# VIVA_PIC16_REV4-5.net
KiCad netlist of a schematic drawn in EAGLE
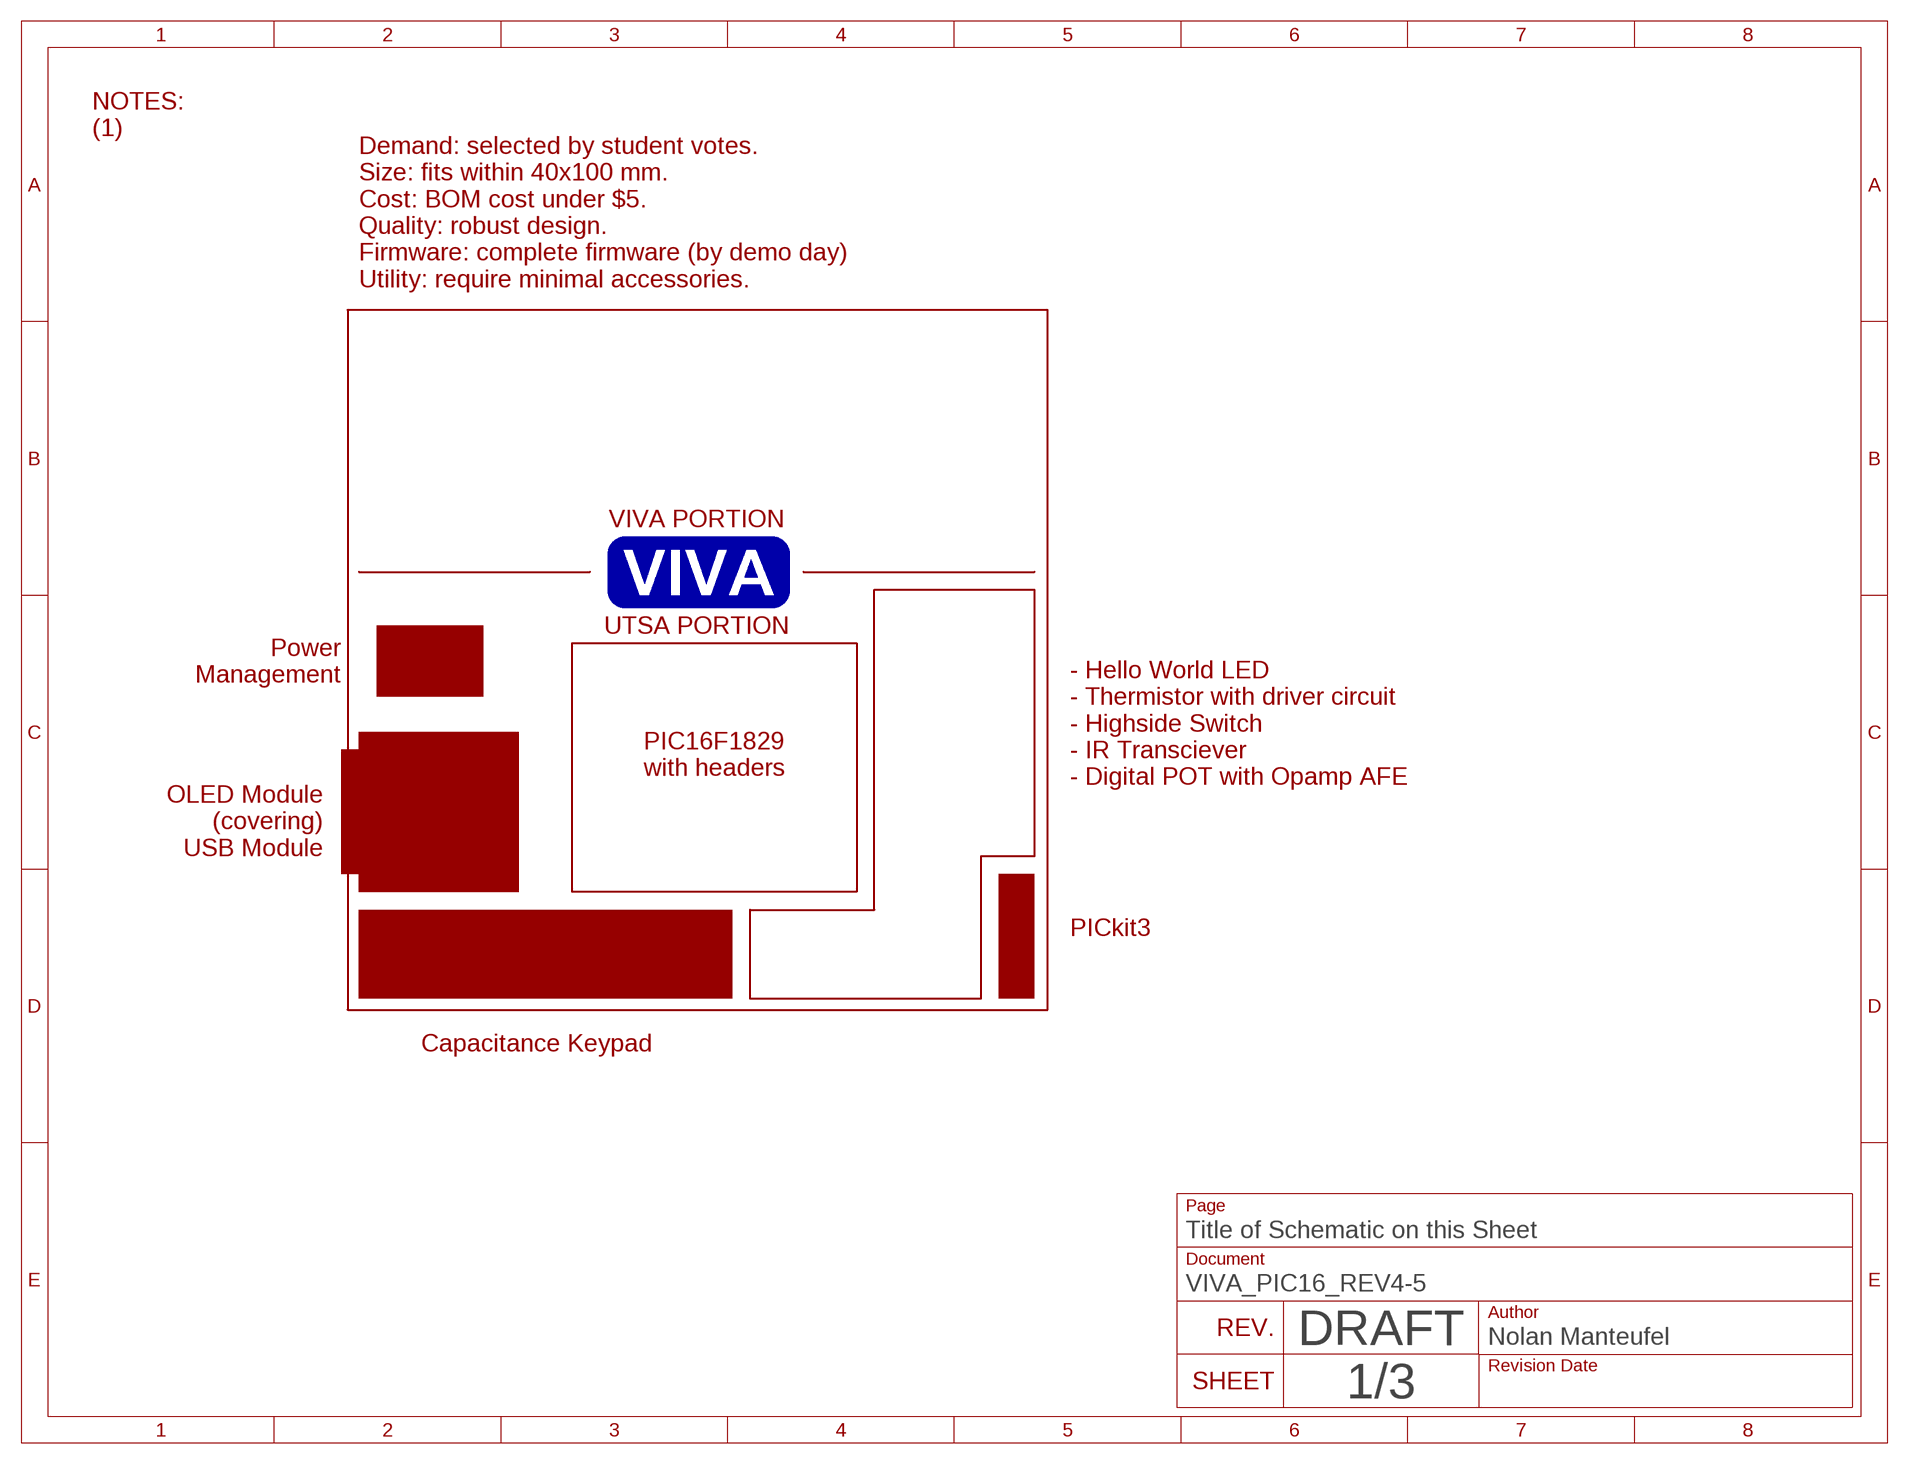
[diagram p0: schematic, sheet 1]
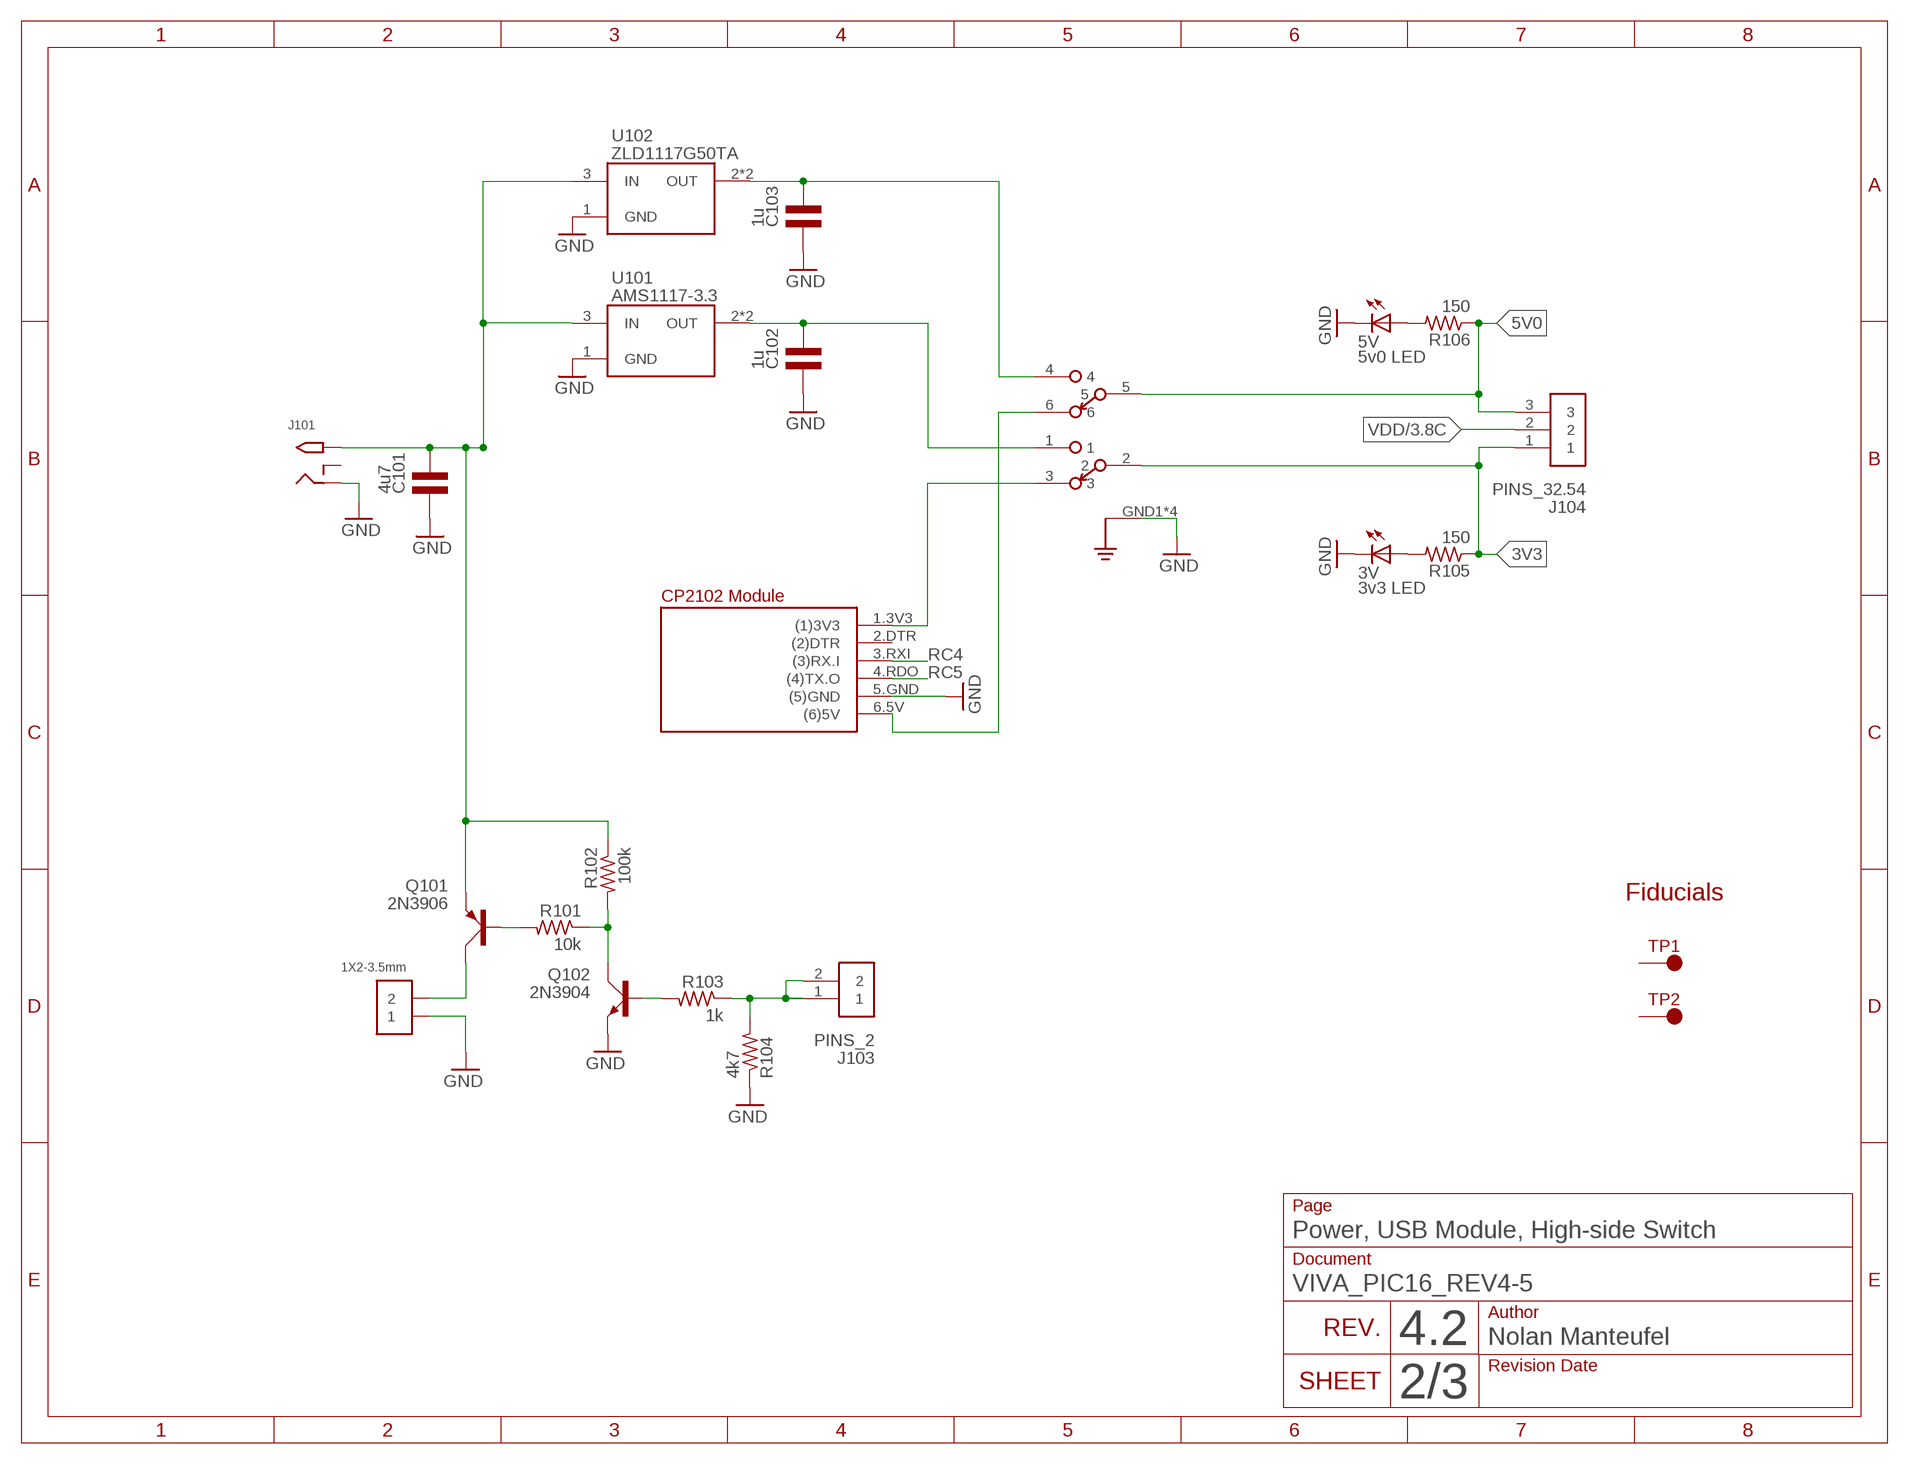
[diagram p1: schematic, sheet 2]
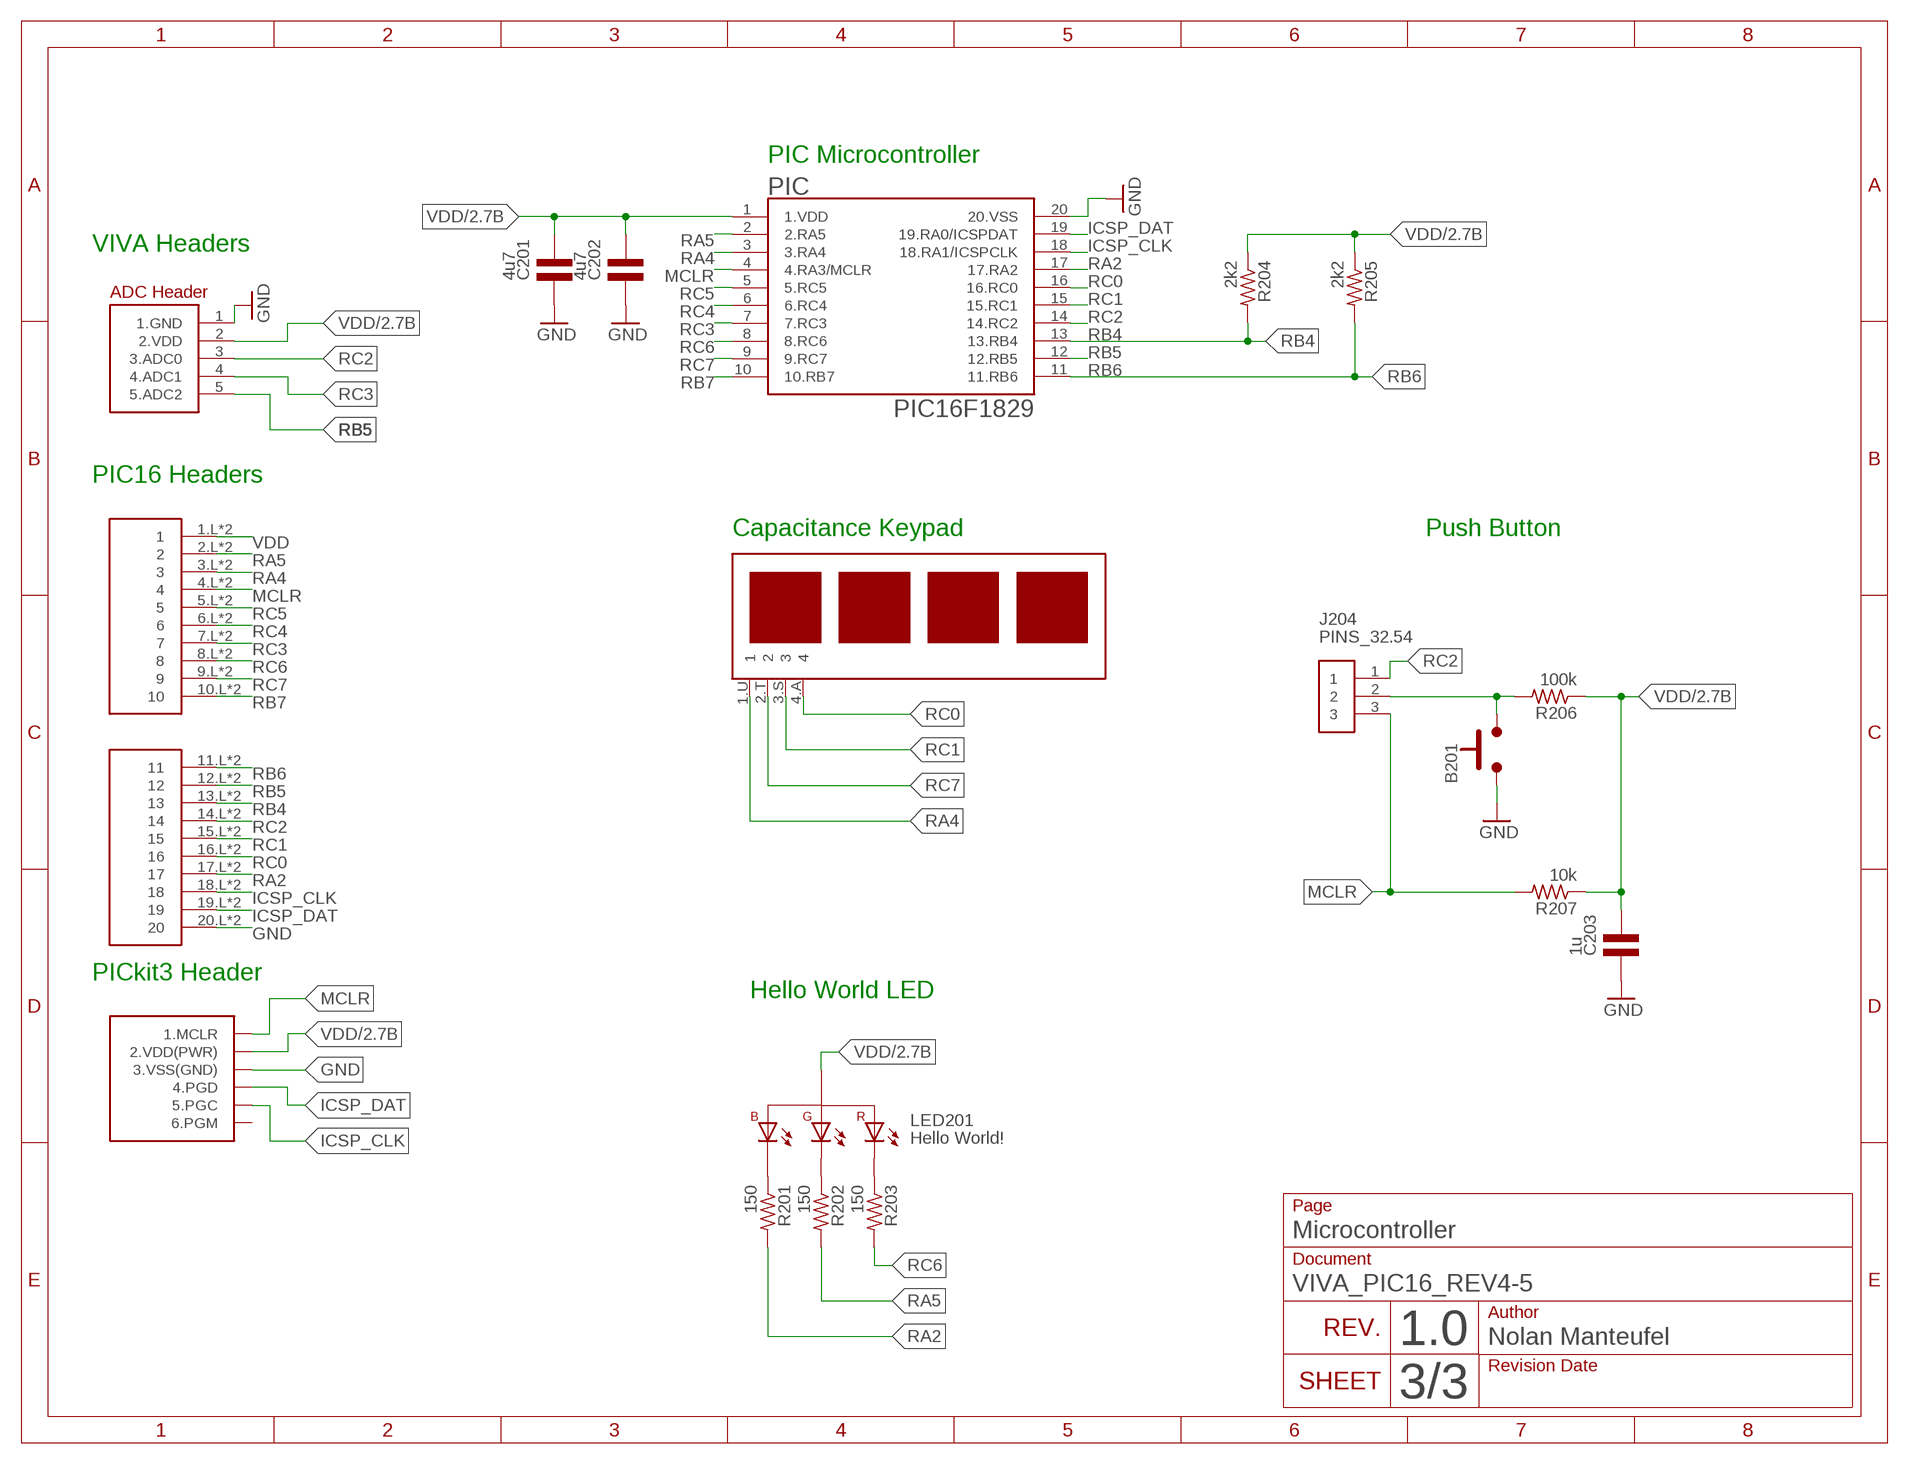
[diagram p2: schematic, sheet 3]

(export (version "E")
  (design (tool "Eeschema 10.0.6"))
  (components
    (comp (ref "3V")
      (value "3v3 LED")
      (footprint "eagle-import:CHIPLED_0805")
      (libsource (lib "eagle-import") (part "LEDCHIPLED_0805"))
    )
    (comp (ref "5V")
      (value "5v0 LED")
      (footprint "eagle-import:CHIPLED_0805")
      (libsource (lib "eagle-import") (part "LEDCHIPLED_0805"))
    )
    (comp (ref "C101")
      (value "4u7")
      (footprint "eagle-import:C0805")
      (libsource (lib "eagle-import") (part "C0805"))
    )
    (comp (ref "C102")
      (value "1u")
      (footprint "eagle-import:C0805")
      (libsource (lib "eagle-import") (part "C0805"))
    )
    (comp (ref "C103")
      (value "1u")
      (footprint "eagle-import:C0805")
      (libsource (lib "eagle-import") (part "C0805"))
    )
    (comp (ref "J101")
      (value "2.1MMJACKTHM")
      (footprint "eagle-import:PJ-102A")
      (libsource (lib "eagle-import") (part "2.1MMJACKTHM"))
    )
    (comp (ref "J102")
      (value "1X2-3.5MM-3.5MM")
      (footprint "eagle-import:1X2-3.5MM")
      (libsource (lib "eagle-import") (part "1X2-3.5MM-3.5MM"))
    )
    (comp (ref "J103")
      (value "PINS_2")
      (footprint "eagle-import:PINS_2")
      (libsource (lib "eagle-import") (part "PINS_2"))
    )
    (comp (ref "J104")
      (value "PINS_32.54")
      (footprint "eagle-import:PINS_3")
      (libsource (lib "eagle-import") (part "PINS_32.54"))
    )
    (comp (ref "M101")
      (value "VIVA_USB-TTL")
      (footprint "eagle-import:VIVA_USB_TTL_SUBTEXT")
      (libsource (lib "eagle-import") (part "VIVA_USB-TTL"))
    )
    (comp (ref "Q101")
      (value "2N3906")
      (footprint "eagle-import:SOT23")
      (libsource (lib "eagle-import") (part "2N3906SOT23"))
    )
    (comp (ref "Q102")
      (value "2N3904")
      (footprint "eagle-import:SOT23")
      (libsource (lib "eagle-import") (part "2N3904SOT23"))
    )
    (comp (ref "R101")
      (value "10k")
      (footprint "eagle-import:R0805")
      (libsource (lib "eagle-import") (part "R-US_R0805"))
    )
    (comp (ref "R102")
      (value "100k")
      (footprint "eagle-import:R0805")
      (libsource (lib "eagle-import") (part "R-US_R0805"))
    )
    (comp (ref "R103")
      (value "1k")
      (footprint "eagle-import:R0805")
      (libsource (lib "eagle-import") (part "R-US_R0805"))
    )
    (comp (ref "R104")
      (value "4k7")
      (footprint "eagle-import:R0805")
      (libsource (lib "eagle-import") (part "R-US_R0805"))
    )
    (comp (ref "R105")
      (value "150")
      (footprint "eagle-import:R0805")
      (libsource (lib "eagle-import") (part "R-US_R0805"))
    )
    (comp (ref "R106")
      (value "150")
      (footprint "eagle-import:R0805")
      (libsource (lib "eagle-import") (part "R-US_R0805"))
    )
    (comp (ref "S101")
      (value "SWITCH_OS202013")
      (footprint "eagle-import:OS202013MT5QN1")
      (libsource (lib "eagle-import") (part "SWITCH_OS202013"))
    )
    (comp (ref "TP1")
      (value "TESTPOINTFIDUCIAL")
      (footprint "eagle-import:FIDUCIAL")
      (libsource (lib "eagle-import") (part "TESTPOINTFIDUCIAL"))
    )
    (comp (ref "TP2")
      (value "TESTPOINTFIDUCIAL")
      (footprint "eagle-import:FIDUCIAL")
      (libsource (lib "eagle-import") (part "TESTPOINTFIDUCIAL"))
    )
    (comp (ref "U101")
      (value "AMS1117-3.3")
      (footprint "eagle-import:SOT223")
      (libsource (lib "eagle-import") (part "REGULATOR_SCHLM1117"))
    )
    (comp (ref "U102")
      (value "ZLD1117G50TA")
      (footprint "eagle-import:SOT223")
      (libsource (lib "eagle-import") (part "REGULATOR_SCHLM1117"))
    )
    (comp (ref "U$1")
      (value "VIVA_LOGO")
      (footprint "eagle-import:VIVA_LOGO")
      (libsource (lib "eagle-import") (part "VIVA_LOGO"))
    )
    (comp (ref "B201")
      (value "PUSHBUTTON6X6MM")
      (footprint "eagle-import:6X6MM")
      (libsource (lib "eagle-import") (part "PUSHBUTTON6X6MM"))
    )
    (comp (ref "C201")
      (value "4u7")
      (footprint "eagle-import:C0805")
      (libsource (lib "eagle-import") (part "C0805"))
    )
    (comp (ref "C202")
      (value "4u7")
      (footprint "eagle-import:C0805")
      (libsource (lib "eagle-import") (part "C0805"))
    )
    (comp (ref "C203")
      (value "1u")
      (footprint "eagle-import:C0805")
      (libsource (lib "eagle-import") (part "C0805"))
    )
    (comp (ref "J201")
      (value "VIVA_PIC16")
      (footprint "eagle-import:VIVA_PIC16")
      (libsource (lib "eagle-import") (part "VIVA_PIC16"))
    )
    (comp (ref "J202")
      (value "VIVA-HEADER-ADCNONAME")
      (footprint "eagle-import:VIVA-HEADER-ADC-NONAME")
      (libsource (lib "eagle-import") (part "VIVA-HEADER-ADCNONAME"))
    )
    (comp (ref "J203")
      (value "PICKIT3")
      (footprint "eagle-import:PICKIT3")
      (libsource (lib "eagle-import") (part "PICKIT3"))
    )
    (comp (ref "J204")
      (value "PINS_32.54")
      (footprint "eagle-import:PINS_3")
      (libsource (lib "eagle-import") (part "PINS_32.54"))
    )
    (comp (ref "LED201")
      (value "Hello World!")
      (footprint "eagle-import:LED_RGB-5050")
      (libsource (lib "eagle-import") (part "RGB_LED"))
    )
    (comp (ref "PIC")
      (value "PIC16F1829")
      (footprint "eagle-import:SOP20-NEW")
      (libsource (lib "eagle-import") (part "PIC16F1829"))
    )
    (comp (ref "R201")
      (value "150")
      (footprint "eagle-import:R0805")
      (libsource (lib "eagle-import") (part "R-US_R0805"))
    )
    (comp (ref "R202")
      (value "150")
      (footprint "eagle-import:R0805")
      (libsource (lib "eagle-import") (part "R-US_R0805"))
    )
    (comp (ref "R203")
      (value "150")
      (footprint "eagle-import:R0805")
      (libsource (lib "eagle-import") (part "R-US_R0805"))
    )
    (comp (ref "R204")
      (value "2k2")
      (footprint "eagle-import:R0805")
      (libsource (lib "eagle-import") (part "R-US_R0805"))
    )
    (comp (ref "R205")
      (value "2k2")
      (footprint "eagle-import:R0805")
      (libsource (lib "eagle-import") (part "R-US_R0805"))
    )
    (comp (ref "R206")
      (value "100k")
      (footprint "eagle-import:R0805")
      (libsource (lib "eagle-import") (part "R-US_R0805"))
    )
    (comp (ref "R207")
      (value "10k")
      (footprint "eagle-import:R0805")
      (libsource (lib "eagle-import") (part "R-US_R0805"))
    )
    (comp (ref "U$201")
      (value "VIVA_UTSA-KEYPAD")
      (footprint "eagle-import:VIVA_UTSA-KEYPAD")
      (libsource (lib "eagle-import") (part "VIVA_UTSA-KEYPAD"))
    )
  )
  (nets
    (net (code "1") (name "3V3") (class "Default")
      (node (ref "J104") (pin "1") (pinfunction "1_1") (pintype "bidirectional"))
      (node (ref "R105") (pin "1") (pinfunction "1_1") (pintype "passive"))
      (node (ref "S101") (pin "2") (pinfunction "2_2") (pintype "bidirectional"))
    )
    (net (code "2") (name "5V0") (class "Default")
      (node (ref "J104") (pin "3") (pinfunction "3_3") (pintype "bidirectional"))
      (node (ref "R106") (pin "1") (pinfunction "1_1") (pintype "passive"))
      (node (ref "S101") (pin "5") (pinfunction "5_5") (pintype "bidirectional"))
    )
    (net (code "3") (name "GND") (class "Default")
      (node (ref "3V") (pin "C") (pinfunction "C_C") (pintype "passive"))
      (node (ref "5V") (pin "C") (pinfunction "C_C") (pintype "passive"))
      (node (ref "B201") (pin "1.A") (pinfunction "1_1.A") (pintype "bidirectional"))
      (node (ref "B201") (pin "2.A") (pinfunction "1_2.A") (pintype "bidirectional"))
      (node (ref "C101") (pin "1") (pinfunction "P$1_1") (pintype "passive"))
      (node (ref "C102") (pin "1") (pinfunction "P$1_1") (pintype "passive"))
      (node (ref "C103") (pin "1") (pinfunction "P$1_1") (pintype "passive"))
      (node (ref "C201") (pin "1") (pinfunction "P$1_1") (pintype "passive"))
      (node (ref "C202") (pin "1") (pinfunction "P$1_1") (pintype "passive"))
      (node (ref "C203") (pin "1") (pinfunction "P$1_1") (pintype "passive"))
      (node (ref "J101") (pin "RING") (pinfunction "RING_RING") (pintype "bidirectional"))
      (node (ref "J102") (pin "1") (pinfunction "1_1") (pintype "passive"))
      (node (ref "J201") (pin "20.L") (pinfunction "20_20.L") (pintype "bidirectional"))
      (node (ref "J201") (pin "20.R") (pinfunction "20_20.R") (pintype "bidirectional"))
      (node (ref "J202") (pin "1") (pinfunction "1.GND_1") (pintype "bidirectional"))
      (node (ref "J203") (pin "3") (pinfunction "3.VSS(GND)_3") (pintype "bidirectional"))
      (node (ref "M101") (pin "5.GND") (pinfunction "(5)GND_5.GND") (pintype "bidirectional"))
      (node (ref "PIC") (pin "20") (pinfunction "20.VSS_20") (pintype "bidirectional"))
      (node (ref "Q102") (pin "2") (pinfunction "E_2") (pintype "passive"))
      (node (ref "R104") (pin "1") (pinfunction "1_1") (pintype "passive"))
      (node (ref "S101") (pin "GND1") (pinfunction "GND_GND1") (pintype "bidirectional"))
      (node (ref "S101") (pin "GND2") (pinfunction "GND_GND2") (pintype "bidirectional"))
      (node (ref "S101") (pin "GND3") (pinfunction "GND_GND3") (pintype "bidirectional"))
      (node (ref "S101") (pin "GND4") (pinfunction "GND_GND4") (pintype "bidirectional"))
      (node (ref "U101") (pin "1") (pinfunction "GND_1") (pintype "bidirectional"))
      (node (ref "U102") (pin "1") (pinfunction "GND_1") (pintype "bidirectional"))
    )
    (net (code "4") (name "ICSP_CLK") (class "Default")
      (node (ref "J201") (pin "18.L") (pinfunction "18_18.L") (pintype "bidirectional"))
      (node (ref "J201") (pin "18.R") (pinfunction "18_18.R") (pintype "bidirectional"))
      (node (ref "J203") (pin "5") (pinfunction "5.PGC_5") (pintype "bidirectional"))
      (node (ref "PIC") (pin "18") (pinfunction "18.RA1/ICSPCLK_18") (pintype "bidirectional"))
    )
    (net (code "5") (name "ICSP_DAT") (class "Default")
      (node (ref "J201") (pin "19.L") (pinfunction "19_19.L") (pintype "bidirectional"))
      (node (ref "J201") (pin "19.R") (pinfunction "19_19.R") (pintype "bidirectional"))
      (node (ref "J203") (pin "4") (pinfunction "4.PGD_4") (pintype "bidirectional"))
      (node (ref "PIC") (pin "19") (pinfunction "19.RA0/ICSPDAT_19") (pintype "bidirectional"))
    )
    (net (code "6") (name "MCLR") (class "Default")
      (node (ref "J201") (pin "4.L") (pinfunction "4_4.L") (pintype "bidirectional"))
      (node (ref "J201") (pin "4.R") (pinfunction "4_4.R") (pintype "bidirectional"))
      (node (ref "J203") (pin "1") (pinfunction "1.MCLR_1") (pintype "bidirectional"))
      (node (ref "J204") (pin "3") (pinfunction "3_3") (pintype "bidirectional"))
      (node (ref "PIC") (pin "4") (pinfunction "4.RA3/MCLR_4") (pintype "bidirectional"))
      (node (ref "R207") (pin "2") (pinfunction "2_2") (pintype "passive"))
    )
    (net (code "7") (name "Net-(3V-PadA)") (class "Default")
      (node (ref "3V") (pin "A") (pinfunction "A_A") (pintype "passive"))
      (node (ref "R105") (pin "2") (pinfunction "2_2") (pintype "passive"))
    )
    (net (code "8") (name "Net-(5V-PadA)") (class "Default")
      (node (ref "5V") (pin "A") (pinfunction "A_A") (pintype "passive"))
      (node (ref "R106") (pin "2") (pinfunction "2_2") (pintype "passive"))
    )
    (net (code "9") (name "Net-(B201-2-Pad3.B)") (class "Default")
      (node (ref "B201") (pin "3.B") (pinfunction "2_3.B") (pintype "bidirectional"))
      (node (ref "B201") (pin "4.B") (pinfunction "2_4.B") (pintype "bidirectional"))
      (node (ref "J204") (pin "2") (pinfunction "2_2") (pintype "bidirectional"))
      (node (ref "R206") (pin "2") (pinfunction "2_2") (pintype "passive"))
    )
    (net (code "10") (name "Net-(C101-P$2)") (class "Default")
      (node (ref "C101") (pin "2") (pinfunction "P$2_2") (pintype "passive"))
      (node (ref "J101") (pin "TIP") (pinfunction "TIP_TIP") (pintype "bidirectional"))
      (node (ref "Q101") (pin "2") (pinfunction "E_2") (pintype "passive"))
      (node (ref "R102") (pin "1") (pinfunction "1_1") (pintype "passive"))
      (node (ref "U101") (pin "3") (pinfunction "IN_3") (pintype "bidirectional"))
      (node (ref "U102") (pin "3") (pinfunction "IN_3") (pintype "bidirectional"))
    )
    (net (code "11") (name "Net-(C102-P$2)") (class "Default")
      (node (ref "C102") (pin "2") (pinfunction "P$2_2") (pintype "passive"))
      (node (ref "S101") (pin "1") (pinfunction "1_1") (pintype "bidirectional"))
      (node (ref "U101") (pin "2") (pinfunction "OUT_2") (pintype "bidirectional"))
      (node (ref "U101") (pin "4.TAB") (pinfunction "OUT_4.TAB") (pintype "bidirectional"))
    )
    (net (code "12") (name "Net-(C103-P$2)") (class "Default")
      (node (ref "C103") (pin "2") (pinfunction "P$2_2") (pintype "passive"))
      (node (ref "S101") (pin "4") (pinfunction "4_4") (pintype "bidirectional"))
      (node (ref "U102") (pin "2") (pinfunction "OUT_2") (pintype "bidirectional"))
      (node (ref "U102") (pin "4.TAB") (pinfunction "OUT_4.TAB") (pintype "bidirectional"))
    )
    (net (code "13") (name "Net-(J103-Pad1)") (class "Default")
      (node (ref "J103") (pin "1") (pinfunction "1_1") (pintype "bidirectional"))
      (node (ref "J103") (pin "2") (pinfunction "2_2") (pintype "bidirectional"))
      (node (ref "R103") (pin "1") (pinfunction "1_1") (pintype "passive"))
      (node (ref "R104") (pin "2") (pinfunction "2_2") (pintype "passive"))
    )
    (net (code "14") (name "Net-(LED201-Pad1.R-)") (class "Default")
      (node (ref "LED201") (pin "1.R-") (pinfunction "1.R-_1.R-") (pintype "passive"))
      (node (ref "R203") (pin "1") (pinfunction "1_1") (pintype "passive"))
    )
    (net (code "15") (name "Net-(LED201-Pad2.G-)") (class "Default")
      (node (ref "LED201") (pin "2.G-") (pinfunction "2.G-_2.G-") (pintype "passive"))
      (node (ref "R202") (pin "1") (pinfunction "1_1") (pintype "passive"))
    )
    (net (code "16") (name "Net-(LED201-Pad4.B-)") (class "Default")
      (node (ref "LED201") (pin "4.B-") (pinfunction "4.B-_4.B-") (pintype "passive"))
      (node (ref "R201") (pin "1") (pinfunction "1_1") (pintype "passive"))
    )
    (net (code "17") (name "Net-(M101-(1)3V3)") (class "Default")
      (node (ref "M101") (pin "1.3V3") (pinfunction "(1)3V3_1.3V3") (pintype "bidirectional"))
      (node (ref "S101") (pin "3") (pinfunction "3_3") (pintype "bidirectional"))
    )
    (net (code "18") (name "Net-(M101-(6)5V)") (class "Default")
      (node (ref "M101") (pin "6.5V") (pinfunction "(6)5V_6.5V") (pintype "bidirectional"))
      (node (ref "S101") (pin "6") (pinfunction "6_6") (pintype "bidirectional"))
    )
    (net (code "19") (name "Net-(Q101-B)") (class "Default")
      (node (ref "Q101") (pin "1") (pinfunction "B_1") (pintype "passive"))
      (node (ref "R101") (pin "2") (pinfunction "2_2") (pintype "passive"))
    )
    (net (code "20") (name "Net-(Q101-C)") (class "Default")
      (node (ref "J102") (pin "2") (pinfunction "2_2") (pintype "passive"))
      (node (ref "Q101") (pin "3") (pinfunction "C_3") (pintype "passive"))
    )
    (net (code "21") (name "Net-(Q102-B)") (class "Default")
      (node (ref "Q102") (pin "1") (pinfunction "B_1") (pintype "passive"))
      (node (ref "R103") (pin "2") (pinfunction "2_2") (pintype "passive"))
    )
    (net (code "22") (name "Net-(Q102-C)") (class "Default")
      (node (ref "Q102") (pin "3") (pinfunction "C_3") (pintype "passive"))
      (node (ref "R101") (pin "1") (pinfunction "1_1") (pintype "passive"))
      (node (ref "R102") (pin "2") (pinfunction "2_2") (pintype "passive"))
    )
    (net (code "23") (name "RA2") (class "Default")
      (node (ref "J201") (pin "17.L") (pinfunction "17_17.L") (pintype "bidirectional"))
      (node (ref "J201") (pin "17.R") (pinfunction "17_17.R") (pintype "bidirectional"))
      (node (ref "PIC") (pin "17") (pinfunction "17.RA2_17") (pintype "bidirectional"))
      (node (ref "R201") (pin "2") (pinfunction "2_2") (pintype "passive"))
    )
    (net (code "24") (name "RA4") (class "Default")
      (node (ref "J201") (pin "3.L") (pinfunction "3_3.L") (pintype "bidirectional"))
      (node (ref "J201") (pin "3.R") (pinfunction "3_3.R") (pintype "bidirectional"))
      (node (ref "PIC") (pin "3") (pinfunction "3.RA4_3") (pintype "bidirectional"))
      (node (ref "U$201") (pin "1.U") (pinfunction "1_1.U") (pintype "bidirectional"))
    )
    (net (code "25") (name "RA5") (class "Default")
      (node (ref "J201") (pin "2.L") (pinfunction "2_2.L") (pintype "bidirectional"))
      (node (ref "J201") (pin "2.R") (pinfunction "2_2.R") (pintype "bidirectional"))
      (node (ref "PIC") (pin "2") (pinfunction "2.RA5_2") (pintype "bidirectional"))
      (node (ref "R202") (pin "2") (pinfunction "2_2") (pintype "passive"))
    )
    (net (code "26") (name "RB4") (class "Default")
      (node (ref "J201") (pin "13.L") (pinfunction "13_13.L") (pintype "bidirectional"))
      (node (ref "J201") (pin "13.R") (pinfunction "13_13.R") (pintype "bidirectional"))
      (node (ref "PIC") (pin "13") (pinfunction "13.RB4_13") (pintype "bidirectional"))
      (node (ref "R204") (pin "2") (pinfunction "2_2") (pintype "passive"))
    )
    (net (code "27") (name "RB5") (class "Default")
      (node (ref "J201") (pin "12.L") (pinfunction "12_12.L") (pintype "bidirectional"))
      (node (ref "J201") (pin "12.R") (pinfunction "12_12.R") (pintype "bidirectional"))
      (node (ref "J202") (pin "5") (pinfunction "5.ADC2_5") (pintype "bidirectional"))
      (node (ref "PIC") (pin "12") (pinfunction "12.RB5_12") (pintype "bidirectional"))
    )
    (net (code "28") (name "RB6") (class "Default")
      (node (ref "J201") (pin "11.L") (pinfunction "11_11.L") (pintype "bidirectional"))
      (node (ref "J201") (pin "11.R") (pinfunction "11_11.R") (pintype "bidirectional"))
      (node (ref "PIC") (pin "11") (pinfunction "11.RB6_11") (pintype "bidirectional"))
      (node (ref "R205") (pin "2") (pinfunction "2_2") (pintype "passive"))
    )
    (net (code "29") (name "RB7") (class "Default")
      (node (ref "J201") (pin "10.L") (pinfunction "10_10.L") (pintype "bidirectional"))
      (node (ref "J201") (pin "10.R") (pinfunction "10_10.R") (pintype "bidirectional"))
      (node (ref "PIC") (pin "10") (pinfunction "10.RB7_10") (pintype "bidirectional"))
    )
    (net (code "30") (name "RC0") (class "Default")
      (node (ref "J201") (pin "16.L") (pinfunction "16_16.L") (pintype "bidirectional"))
      (node (ref "J201") (pin "16.R") (pinfunction "16_16.R") (pintype "bidirectional"))
      (node (ref "PIC") (pin "16") (pinfunction "16.RC0_16") (pintype "bidirectional"))
      (node (ref "U$201") (pin "4.A") (pinfunction "4_4.A") (pintype "bidirectional"))
    )
    (net (code "31") (name "RC1") (class "Default")
      (node (ref "J201") (pin "15.L") (pinfunction "15_15.L") (pintype "bidirectional"))
      (node (ref "J201") (pin "15.R") (pinfunction "15_15.R") (pintype "bidirectional"))
      (node (ref "PIC") (pin "15") (pinfunction "15.RC1_15") (pintype "bidirectional"))
      (node (ref "U$201") (pin "3.S") (pinfunction "3_3.S") (pintype "bidirectional"))
    )
    (net (code "32") (name "RC2") (class "Default")
      (node (ref "J201") (pin "14.L") (pinfunction "14_14.L") (pintype "bidirectional"))
      (node (ref "J201") (pin "14.R") (pinfunction "14_14.R") (pintype "bidirectional"))
      (node (ref "J202") (pin "3") (pinfunction "3.ADC0_3") (pintype "bidirectional"))
      (node (ref "J204") (pin "1") (pinfunction "1_1") (pintype "bidirectional"))
      (node (ref "PIC") (pin "14") (pinfunction "14.RC2_14") (pintype "bidirectional"))
    )
    (net (code "33") (name "RC3") (class "Default")
      (node (ref "J201") (pin "7.L") (pinfunction "7_7.L") (pintype "bidirectional"))
      (node (ref "J201") (pin "7.R") (pinfunction "7_7.R") (pintype "bidirectional"))
      (node (ref "J202") (pin "4") (pinfunction "4.ADC1_4") (pintype "bidirectional"))
      (node (ref "PIC") (pin "7") (pinfunction "7.RC3_7") (pintype "bidirectional"))
    )
    (net (code "34") (name "RC4") (class "Default")
      (node (ref "J201") (pin "6.L") (pinfunction "6_6.L") (pintype "bidirectional"))
      (node (ref "J201") (pin "6.R") (pinfunction "6_6.R") (pintype "bidirectional"))
      (node (ref "M101") (pin "3.RXI") (pinfunction "(3)RX.I_3.RXI") (pintype "bidirectional"))
      (node (ref "PIC") (pin "6") (pinfunction "6.RC4_6") (pintype "bidirectional"))
    )
    (net (code "35") (name "RC5") (class "Default")
      (node (ref "J201") (pin "5.L") (pinfunction "5_5.L") (pintype "bidirectional"))
      (node (ref "J201") (pin "5.R") (pinfunction "5_5.R") (pintype "bidirectional"))
      (node (ref "M101") (pin "4.RDO") (pinfunction "(4)TX.O_4.RDO") (pintype "bidirectional"))
      (node (ref "PIC") (pin "5") (pinfunction "5.RC5_5") (pintype "bidirectional"))
    )
    (net (code "36") (name "RC6") (class "Default")
      (node (ref "J201") (pin "8.L") (pinfunction "8_8.L") (pintype "bidirectional"))
      (node (ref "J201") (pin "8.R") (pinfunction "8_8.R") (pintype "bidirectional"))
      (node (ref "PIC") (pin "8") (pinfunction "8.RC6_8") (pintype "bidirectional"))
      (node (ref "R203") (pin "2") (pinfunction "2_2") (pintype "passive"))
    )
    (net (code "37") (name "RC7") (class "Default")
      (node (ref "J201") (pin "9.L") (pinfunction "9_9.L") (pintype "bidirectional"))
      (node (ref "J201") (pin "9.R") (pinfunction "9_9.R") (pintype "bidirectional"))
      (node (ref "PIC") (pin "9") (pinfunction "9.RC7_9") (pintype "bidirectional"))
      (node (ref "U$201") (pin "2.T") (pinfunction "2_2.T") (pintype "bidirectional"))
    )
    (net (code "38") (name "VDD") (class "Default")
      (node (ref "C201") (pin "2") (pinfunction "P$2_2") (pintype "passive"))
      (node (ref "C202") (pin "2") (pinfunction "P$2_2") (pintype "passive"))
      (node (ref "C203") (pin "2") (pinfunction "P$2_2") (pintype "passive"))
      (node (ref "J104") (pin "2") (pinfunction "2_2") (pintype "bidirectional"))
      (node (ref "J201") (pin "1.L") (pinfunction "1_1.L") (pintype "bidirectional"))
      (node (ref "J201") (pin "1.R") (pinfunction "1_1.R") (pintype "bidirectional"))
      (node (ref "J202") (pin "2") (pinfunction "2.VDD_2") (pintype "bidirectional"))
      (node (ref "J203") (pin "2") (pinfunction "2.VDD(PWR)_2") (pintype "bidirectional"))
      (node (ref "LED201") (pin "3.+") (pinfunction "3.+_3.+") (pintype "passive"))
      (node (ref "PIC") (pin "1") (pinfunction "1.VDD_1") (pintype "bidirectional"))
      (node (ref "R204") (pin "1") (pinfunction "1_1") (pintype "passive"))
      (node (ref "R205") (pin "1") (pinfunction "1_1") (pintype "passive"))
      (node (ref "R206") (pin "1") (pinfunction "1_1") (pintype "passive"))
      (node (ref "R207") (pin "1") (pinfunction "1_1") (pintype "passive"))
    )
    (net (code "39") (name "unconnected-(J101-PadRING_SW)") (class "Default")
      (node (ref "J101") (pin "RING_SW") (pinfunction "RING_SW_RING_SW") (pintype "bidirectional"))
    )
    (net (code "40") (name "unconnected-(J203-6.PGM-Pad6)") (class "Default")
      (node (ref "J203") (pin "6") (pinfunction "6.PGM_6") (pintype "bidirectional"))
    )
    (net (code "41") (name "unconnected-(M101-(2)DTR-Pad2.DTR)") (class "Default")
      (node (ref "M101") (pin "2.DTR") (pinfunction "(2)DTR_2.DTR") (pintype "bidirectional"))
    )
    (net (code "42") (name "unconnected-(TP1-P$1-PadFIDUCIAL)") (class "Default")
      (node (ref "TP1") (pin "FIDUCIAL") (pinfunction "P$1_FIDUCIAL") (pintype "bidirectional"))
    )
    (net (code "43") (name "unconnected-(TP2-P$1-PadFIDUCIAL)") (class "Default")
      (node (ref "TP2") (pin "FIDUCIAL") (pinfunction "P$1_FIDUCIAL") (pintype "bidirectional"))
    )
  )
)
